# DRS_POT_LPFs.net
KiCad netlist of a schematic drawn in Altium Designer
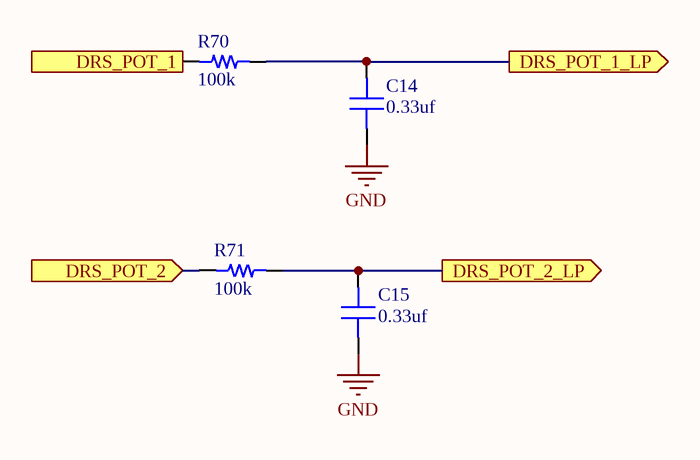
[diagram p0: DRS_POT_LPFs.SchDoc]

(export (version "E")
  (design (tool "Eeschema 10.0.6"))
  (components
    (comp (ref "C14")
      (value "0.33uf")
      (footprint "CAP 0603/1608")
      (fields
        (field (name "Comment") "Capacitor MLCC 0.33uf 16V CAP 0603/1608")
        (field (name "CREATED_BY") "Nick Mah")
      )
      (libsource (lib "Altium-Lib") (part "Capacitor"))
    )
    (comp (ref "C15")
      (value "0.33uf")
      (footprint "CAP 0603/1608")
      (fields
        (field (name "Comment") "Capacitor MLCC 0.33uf 16V CAP 0603/1608")
        (field (name "CREATED_BY") "Nick Mah")
      )
      (libsource (lib "Altium-Lib") (part "Capacitor"))
    )
    (comp (ref "R70")
      (value "100k")
      (footprint "RES 0603/1608")
      (fields
        (field (name "TOLERANCE") "1%")
        (field (name "POWER") "1/10W")
        (field (name "Comment") "Resistor 100k 0603 1/10W 1%")
        (field (name "CREATED_BY") "Nick Mah")
      )
      (libsource (lib "Altium-Lib") (part "Resistor"))
    )
    (comp (ref "R71")
      (value "100k")
      (footprint "RES 0603/1608")
      (fields
        (field (name "TOLERANCE") "1%")
        (field (name "POWER") "1/10W")
        (field (name "Comment") "Resistor 100k 0603 1/10W 1%")
        (field (name "CREATED_BY") "Nick Mah")
      )
      (libsource (lib "Altium-Lib") (part "Resistor"))
    )
  )
  (nets
    (net (code "1") (name "/DRS_POT_1") (class "Default")
      (node (ref "R70") (pin "1") (pinfunction "1_1") (pintype "passive"))
    )
    (net (code "2") (name "/DRS_POT_1_LP") (class "Default")
      (node (ref "C14") (pin "2") (pinfunction "2_2") (pintype "passive"))
      (node (ref "R70") (pin "2") (pinfunction "2_2") (pintype "passive"))
    )
    (net (code "3") (name "/DRS_POT_2") (class "Default")
      (node (ref "R71") (pin "1") (pinfunction "1_1") (pintype "passive"))
    )
    (net (code "4") (name "/DRS_POT_2_LP") (class "Default")
      (node (ref "C15") (pin "2") (pinfunction "2_2") (pintype "passive"))
      (node (ref "R71") (pin "2") (pinfunction "2_2") (pintype "passive"))
    )
    (net (code "5") (name "GND") (class "Default")
      (node (ref "C14") (pin "1") (pinfunction "1_1") (pintype "passive"))
      (node (ref "C15") (pin "1") (pinfunction "1_1") (pintype "passive"))
    )
  )
)
